# DRV_RGB_PRG.net
KiCad netlist of a schematic drawn in EAGLE
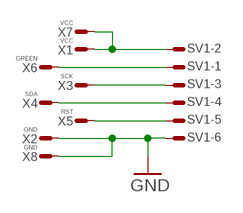
[diagram p0: schematic, sheet 1]

(export (version "E")
  (design (tool "Eeschema 10.0.6"))
  (components
    (comp (ref "SV1")
      (value "ML6ES")
      (footprint "eagle-import:ML6S")
      (libsource (lib "eagle-import") (part "ML6ES"))
    )
    (comp (ref "X1")
      (value "VCC")
      (footprint "eagle-import:T1.6_0.9")
      (libsource (lib "eagle-import") (part "WIREPADT1.6/0.9"))
    )
    (comp (ref "X2")
      (value "GND")
      (footprint "eagle-import:T1.6_0.9")
      (libsource (lib "eagle-import") (part "WIREPADT1.6/0.9"))
    )
    (comp (ref "X3")
      (value "SCK")
      (footprint "eagle-import:T1.6_0.9")
      (libsource (lib "eagle-import") (part "WIREPADT1.6/0.9"))
    )
    (comp (ref "X4")
      (value "SDA")
      (footprint "eagle-import:T1.6_0.9")
      (libsource (lib "eagle-import") (part "WIREPADT1.6/0.9"))
    )
    (comp (ref "X5")
      (value "RST")
      (footprint "eagle-import:T1.6_0.9")
      (libsource (lib "eagle-import") (part "WIREPADT1.6/0.9"))
    )
    (comp (ref "X6")
      (value "GREEN")
      (footprint "eagle-import:T1.6_0.9")
      (libsource (lib "eagle-import") (part "WIREPADT1.6/0.9"))
    )
    (comp (ref "X7")
      (value "VCC")
      (footprint "eagle-import:T1.6_0.9")
      (libsource (lib "eagle-import") (part "WIREPADT1.6/0.9"))
    )
    (comp (ref "X8")
      (value "GND")
      (footprint "eagle-import:T1.6_0.9")
      (libsource (lib "eagle-import") (part "WIREPADT1.6/0.9"))
    )
  )
  (nets
    (net (code "1") (name "GND") (class "Default")
      (node (ref "SV1") (pin "6") (pinfunction "S_6") (pintype "passive"))
      (node (ref "X2") (pin "1") (pinfunction "S_1") (pintype "passive"))
      (node (ref "X8") (pin "1") (pinfunction "S_1") (pintype "passive"))
    )
    (net (code "2") (name "Net-(SV1A-S)") (class "Default")
      (node (ref "SV1") (pin "1") (pinfunction "S_1") (pintype "passive"))
      (node (ref "X6") (pin "1") (pinfunction "S_1") (pintype "passive"))
    )
    (net (code "3") (name "Net-(SV1B-S)") (class "Default")
      (node (ref "SV1") (pin "2") (pinfunction "S_2") (pintype "passive"))
      (node (ref "X1") (pin "1") (pinfunction "S_1") (pintype "passive"))
      (node (ref "X7") (pin "1") (pinfunction "S_1") (pintype "passive"))
    )
    (net (code "4") (name "Net-(SV1C-S)") (class "Default")
      (node (ref "SV1") (pin "3") (pinfunction "S_3") (pintype "passive"))
      (node (ref "X3") (pin "1") (pinfunction "S_1") (pintype "passive"))
    )
    (net (code "5") (name "Net-(SV1D-S)") (class "Default")
      (node (ref "SV1") (pin "4") (pinfunction "S_4") (pintype "passive"))
      (node (ref "X4") (pin "1") (pinfunction "S_1") (pintype "passive"))
    )
    (net (code "6") (name "Net-(SV1E-S)") (class "Default")
      (node (ref "SV1") (pin "5") (pinfunction "S_5") (pintype "passive"))
      (node (ref "X5") (pin "1") (pinfunction "S_1") (pintype "passive"))
    )
  )
)
